# Module.net
KiCad netlist of a schematic drawn in EAGLE
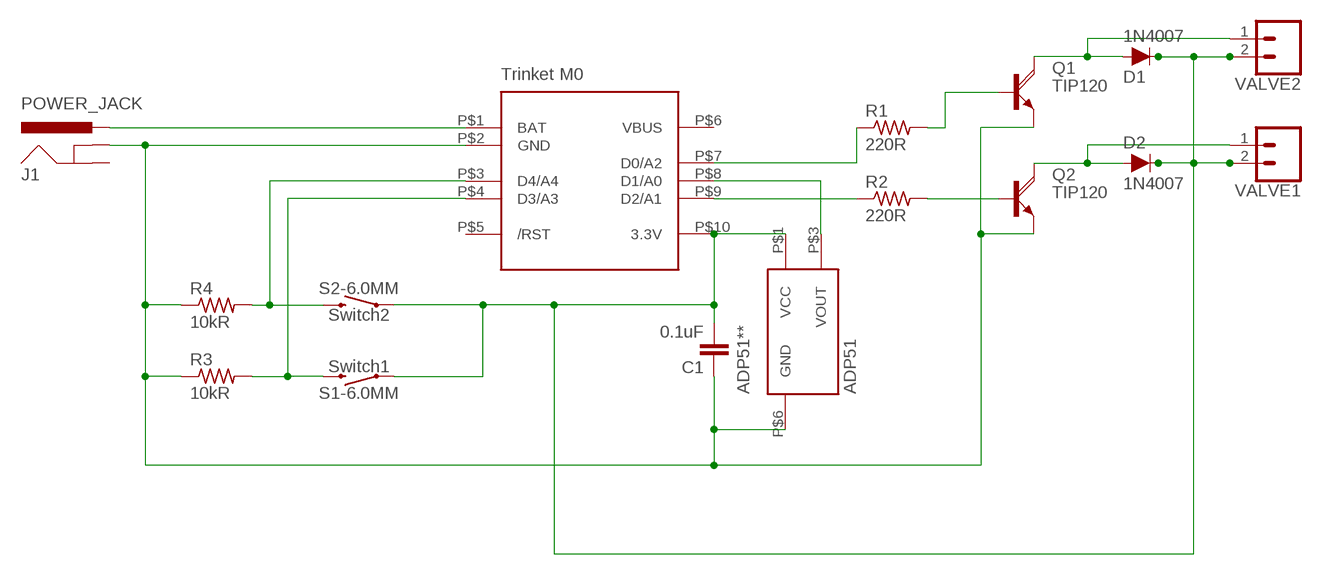
[diagram p0: schematic, sheet 1]

(export (version "E")
  (design (tool "Eeschema 10.0.6"))
  (components
    (comp (ref "C1")
      (value "0.1uF")
      (footprint "eagle-import:CAP-PTH-SMALL-KIT")
      (libsource (lib "eagle-import") (part "0.1UF-KIT-EZ-50V-20%"))
    )
    (comp (ref "D1")
      (value "1N4007")
      (footprint "eagle-import:DIODE-1N4148")
      (libsource (lib "eagle-import") (part "DIODE-1N4148"))
    )
    (comp (ref "D2")
      (value "1N4007")
      (footprint "eagle-import:DIODE-1N4148")
      (libsource (lib "eagle-import") (part "DIODE-1N4148"))
    )
    (comp (ref "J1")
      (value "POWER_JACK")
      (footprint "eagle-import:POWER_JACK_PTH")
      (libsource (lib "eagle-import") (part "POWER_JACK"))
    )
    (comp (ref "Q1")
      (value "TIP120")
      (footprint "eagle-import:TO126AV")
      (libsource (lib "eagle-import") (part "BD679"))
    )
    (comp (ref "Q2")
      (value "TIP120")
      (footprint "eagle-import:TO126AV")
      (libsource (lib "eagle-import") (part "BD679"))
    )
    (comp (ref "R1")
      (value "220R")
      (footprint "eagle-import:0207_10")
      (libsource (lib "eagle-import") (part "R-US_0207/10"))
    )
    (comp (ref "R2")
      (value "220R")
      (footprint "eagle-import:0207_10")
      (libsource (lib "eagle-import") (part "R-US_0207/10"))
    )
    (comp (ref "R3")
      (value "10kR")
      (footprint "eagle-import:0207_10")
      (libsource (lib "eagle-import") (part "R-US_0207/10"))
    )
    (comp (ref "R4")
      (value "10kR")
      (footprint "eagle-import:0207_10")
      (libsource (lib "eagle-import") (part "R-US_0207/10"))
    )
    (comp (ref "S1-6.0MM")
      (value "Switch1")
      (footprint "eagle-import:TACTILE_SWITCH_PTH_6.0MM")
      (libsource (lib "eagle-import") (part "MOMENTARY-SWITCH-SPST-PTH-6.0MM"))
    )
    (comp (ref "S2-6.0MM")
      (value "Switch2")
      (footprint "eagle-import:TACTILE_SWITCH_PTH_6.0MM")
      (libsource (lib "eagle-import") (part "MOMENTARY-SWITCH-SPST-PTH-6.0MM"))
    )
    (comp (ref "U$1")
      (value "TRINKET-M0")
      (footprint "eagle-import:TRINKET-M0")
      (libsource (lib "eagle-import") (part "TRINKET-M0"))
    )
    (comp (ref "U$2")
      (value "ADP51")
      (footprint "eagle-import:ADP5121")
      (libsource (lib "eagle-import") (part "ADP51"))
    )
    (comp (ref "VALVE1")
      (value "CONN_02POLAR")
      (footprint "eagle-import:MOLEX-1X2")
      (libsource (lib "eagle-import") (part "CONN_02POLAR"))
    )
    (comp (ref "VALVE2")
      (value "CONN_02POLAR")
      (footprint "eagle-import:MOLEX-1X2")
      (libsource (lib "eagle-import") (part "CONN_02POLAR"))
    )
  )
  (nets
    (net (code "1") (name "Net-(D1-PadA)") (class "Default")
      (node (ref "D1") (pin "A") (pinfunction "A_A") (pintype "passive"))
      (node (ref "Q1") (pin "C") (pinfunction "C_C") (pintype "passive"))
      (node (ref "VALVE2") (pin "1") (pinfunction "1_1") (pintype "passive"))
    )
    (net (code "2") (name "Net-(D2-PadA)") (class "Default")
      (node (ref "D2") (pin "A") (pinfunction "A_A") (pintype "passive"))
      (node (ref "Q2") (pin "C") (pinfunction "C_C") (pintype "passive"))
      (node (ref "VALVE1") (pin "1") (pinfunction "1_1") (pintype "passive"))
    )
    (net (code "3") (name "Net-(Q1-PadB)") (class "Default")
      (node (ref "Q1") (pin "B") (pinfunction "B_B") (pintype "passive"))
      (node (ref "R1") (pin "2") (pinfunction "2_2") (pintype "passive"))
    )
    (net (code "4") (name "Net-(Q2-PadB)") (class "Default")
      (node (ref "Q2") (pin "B") (pinfunction "B_B") (pintype "passive"))
      (node (ref "R2") (pin "2") (pinfunction "2_2") (pintype "passive"))
    )
    (net (code "5") (name "Net-(S1-6.0MM-2)") (class "Default")
      (node (ref "R3") (pin "2") (pinfunction "2_2") (pintype "passive"))
      (node (ref "S1-6.0MM") (pin "3") (pinfunction "2_3") (pintype "passive"))
      (node (ref "U$1") (pin "P$4") (pinfunction "D3/A3_P$4") (pintype "bidirectional"))
    )
    (net (code "6") (name "Net-(S2-6.0MM-2)") (class "Default")
      (node (ref "R4") (pin "2") (pinfunction "2_2") (pintype "passive"))
      (node (ref "S2-6.0MM") (pin "3") (pinfunction "2_3") (pintype "passive"))
      (node (ref "U$1") (pin "P$3") (pinfunction "D4/A4_P$3") (pintype "bidirectional"))
    )
    (net (code "7") (name "Net-(U$1-3.3V)") (class "Default")
      (node (ref "C1") (pin "2") (pinfunction "2_2") (pintype "passive"))
      (node (ref "D1") (pin "C") (pinfunction "C_C") (pintype "passive"))
      (node (ref "D2") (pin "C") (pinfunction "C_C") (pintype "passive"))
      (node (ref "S1-6.0MM") (pin "1") (pinfunction "1_1") (pintype "passive"))
      (node (ref "S2-6.0MM") (pin "1") (pinfunction "1_1") (pintype "passive"))
      (node (ref "U$1") (pin "P$10") (pinfunction "3.3V_P$10") (pintype "bidirectional"))
      (node (ref "U$2") (pin "P$1") (pinfunction "VCC_P$1") (pintype "bidirectional"))
      (node (ref "VALVE1") (pin "2") (pinfunction "2_2") (pintype "passive"))
      (node (ref "VALVE2") (pin "2") (pinfunction "2_2") (pintype "passive"))
    )
    (net (code "8") (name "Net-(U$1-BAT)") (class "Default")
      (node (ref "J1") (pin "PWR") (pinfunction "PWR_PWR") (pintype "bidirectional"))
      (node (ref "U$1") (pin "P$1") (pinfunction "BAT_P$1") (pintype "bidirectional"))
    )
    (net (code "9") (name "Net-(U$1-D0{slash}A2)") (class "Default")
      (node (ref "R1") (pin "1") (pinfunction "1_1") (pintype "passive"))
      (node (ref "U$1") (pin "P$7") (pinfunction "D0/A2_P$7") (pintype "bidirectional"))
    )
    (net (code "10") (name "Net-(U$1-D1{slash}A0)") (class "Default")
      (node (ref "U$1") (pin "P$8") (pinfunction "D1/A0_P$8") (pintype "bidirectional"))
      (node (ref "U$2") (pin "P$3") (pinfunction "VOUT_P$3") (pintype "bidirectional"))
    )
    (net (code "11") (name "Net-(U$1-D2{slash}A1)") (class "Default")
      (node (ref "R2") (pin "1") (pinfunction "1_1") (pintype "passive"))
      (node (ref "U$1") (pin "P$9") (pinfunction "D2/A1_P$9") (pintype "bidirectional"))
    )
    (net (code "12") (name "Net-(U$1-GND)") (class "Default")
      (node (ref "C1") (pin "1") (pinfunction "1_1") (pintype "passive"))
      (node (ref "J1") (pin "GNDBREAK") (pinfunction "GNDBREAK_GNDBREAK") (pintype "bidirectional"))
      (node (ref "Q1") (pin "E") (pinfunction "E_E") (pintype "passive"))
      (node (ref "Q2") (pin "E") (pinfunction "E_E") (pintype "passive"))
      (node (ref "R3") (pin "1") (pinfunction "1_1") (pintype "passive"))
      (node (ref "R4") (pin "1") (pinfunction "1_1") (pintype "passive"))
      (node (ref "U$1") (pin "P$2") (pinfunction "GND_P$2") (pintype "bidirectional"))
      (node (ref "U$2") (pin "P$6") (pinfunction "GND_P$6") (pintype "bidirectional"))
    )
    (net (code "13") (name "unconnected-(J1-PadGND)") (class "Default")
      (node (ref "J1") (pin "GND") (pinfunction "GND_GND") (pintype "bidirectional"))
    )
    (net (code "14") (name "unconnected-(U$1-VBUS-PadP$6)") (class "Default")
      (node (ref "U$1") (pin "P$6") (pinfunction "VBUS_P$6") (pintype "bidirectional"))
    )
    (net (code "15") (name "unconnected-(U$1-{slash}RST-PadP$5)") (class "Default")
      (node (ref "U$1") (pin "P$5") (pinfunction "/RST_P$5") (pintype "bidirectional"))
    )
  )
)
